# Dout32x.net
KiCad netlist of a schematic drawn in Altium Designer
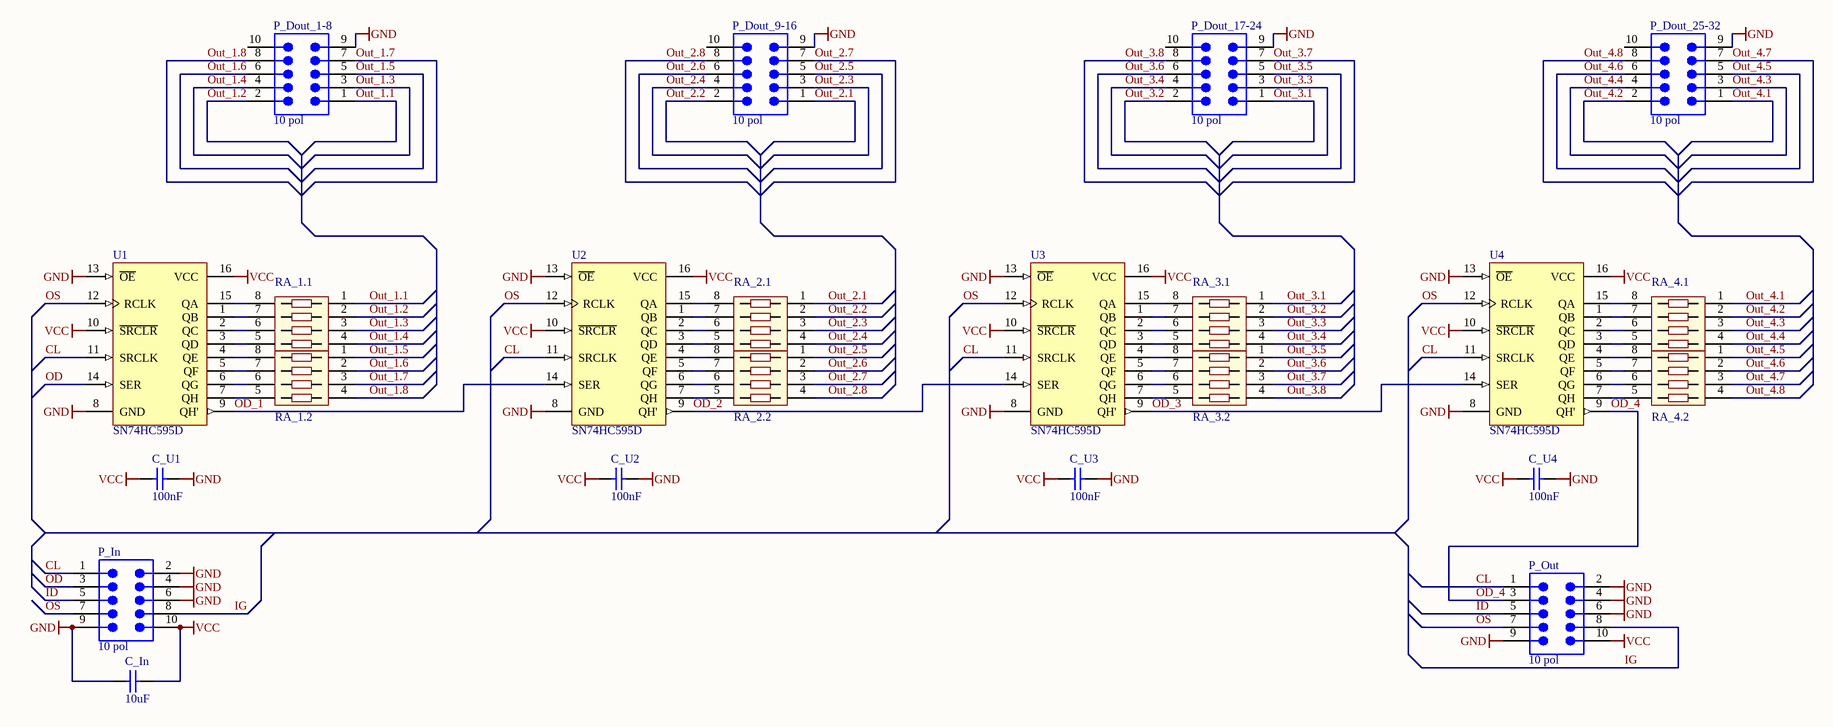
[diagram p0: Dout32x.SchDoc]

(export (version "E")
  (design (tool "Eeschema 10.0.6"))
  (components
    (comp (ref "C_In")
      (value "10uF")
      (footprint "1608[0603]")
      (description "Capacitor (Semiconductor SIM Model)")
      (fields (field (name "Comment") "Cap Semi") (field (name "PUBLISHER") "Altium Limited"))
      (libsource (lib "Miscellaneous Devices") (part "Cap Semi"))
    )
    (comp (ref "C_U1")
      (value "100nF")
      (footprint "1608[0603]")
      (description "Capacitor (Semiconductor SIM Model)")
      (fields (field (name "Comment") "Cap Semi") (field (name "PUBLISHER") "Altium Limited"))
      (libsource (lib "Miscellaneous Devices") (part "Cap Semi"))
    )
    (comp (ref "C_U2")
      (value "100nF")
      (footprint "1608[0603]")
      (description "Capacitor (Semiconductor SIM Model)")
      (fields (field (name "Comment") "Cap Semi") (field (name "PUBLISHER") "Altium Limited"))
      (libsource (lib "Miscellaneous Devices") (part "Cap Semi"))
    )
    (comp (ref "C_U3")
      (value "100nF")
      (footprint "1608[0603]")
      (description "Capacitor (Semiconductor SIM Model)")
      (fields (field (name "Comment") "Cap Semi") (field (name "PUBLISHER") "Altium Limited"))
      (libsource (lib "Miscellaneous Devices") (part "Cap Semi"))
    )
    (comp (ref "C_U4")
      (value "100nF")
      (footprint "1608[0603]")
      (description "Capacitor (Semiconductor SIM Model)")
      (fields (field (name "Comment") "Cap Semi") (field (name "PUBLISHER") "Altium Limited"))
      (libsource (lib "Miscellaneous Devices") (part "Cap Semi"))
    )
    (comp (ref "P_Dout_1-8")
      (value "10 pol")
      (footprint "918510x324")
      (fields (field (name "PUBLISHER") "Altium Limited"))
      (libsource (lib "HARTING IDC 2.54mm Pitch") (part "09 18 510 6324"))
    )
    (comp (ref "P_Dout_9-16")
      (value "10 pol")
      (footprint "918510x324")
      (fields (field (name "PUBLISHER") "Altium Limited"))
      (libsource (lib "HARTING IDC 2.54mm Pitch") (part "09 18 510 6324"))
    )
    (comp (ref "P_Dout_17-24")
      (value "10 pol")
      (footprint "918510x324")
      (fields (field (name "PUBLISHER") "Altium Limited"))
      (libsource (lib "HARTING IDC 2.54mm Pitch") (part "09 18 510 6324"))
    )
    (comp (ref "P_Dout_25-32")
      (value "10 pol")
      (footprint "918510x324")
      (fields (field (name "PUBLISHER") "Altium Limited"))
      (libsource (lib "HARTING IDC 2.54mm Pitch") (part "09 18 510 6324"))
    )
    (comp (ref "P_In")
      (value "10 pol")
      (footprint "918510x324")
      (fields (field (name "PUBLISHER") "Altium Limited"))
      (libsource (lib "") (part "09 18 510 6324_1"))
    )
    (comp (ref "P_Out")
      (value "10 pol")
      (footprint "918510x324")
      (fields (field (name "PUBLISHER") "Altium Limited"))
      (libsource (lib "") (part "09 18 510 6324_1"))
    )
    (comp (ref "RA_1.1")
      (value "EXB38")
      (footprint "Panasonic EXB38V:EXB38")
      (fields (field (name "PUBLISHER") "Altium Limited"))
      (libsource (lib "Panasonic Resistor Array") (part "4 Resistors Parallel"))
    )
    (comp (ref "RA_1.2")
      (value "EXB38")
      (footprint "Panasonic EXB38V:EXB38")
      (fields (field (name "PUBLISHER") "Altium Limited"))
      (libsource (lib "Panasonic Resistor Array") (part "4 Resistors Parallel"))
    )
    (comp (ref "RA_2.1")
      (value "EXB38")
      (footprint "Panasonic EXB38V:EXB38")
      (fields (field (name "PUBLISHER") "Altium Limited"))
      (libsource (lib "Panasonic Resistor Array") (part "4 Resistors Parallel"))
    )
    (comp (ref "RA_2.2")
      (value "EXB38")
      (footprint "Panasonic EXB38V:EXB38")
      (fields (field (name "PUBLISHER") "Altium Limited"))
      (libsource (lib "Panasonic Resistor Array") (part "4 Resistors Parallel"))
    )
    (comp (ref "RA_3.1")
      (value "EXB38")
      (footprint "Panasonic EXB38V:EXB38")
      (fields (field (name "PUBLISHER") "Altium Limited"))
      (libsource (lib "Panasonic Resistor Array") (part "4 Resistors Parallel"))
    )
    (comp (ref "RA_3.2")
      (value "EXB38")
      (footprint "Panasonic EXB38V:EXB38")
      (fields (field (name "PUBLISHER") "Altium Limited"))
      (libsource (lib "Panasonic Resistor Array") (part "4 Resistors Parallel"))
    )
    (comp (ref "RA_4.1")
      (value "EXB38")
      (footprint "Panasonic EXB38V:EXB38")
      (fields (field (name "PUBLISHER") "Altium Limited"))
      (libsource (lib "Panasonic Resistor Array") (part "4 Resistors Parallel"))
    )
    (comp (ref "RA_4.2")
      (value "EXB38")
      (footprint "Panasonic EXB38V:EXB38")
      (fields (field (name "PUBLISHER") "Altium Limited"))
      (libsource (lib "Panasonic Resistor Array") (part "4 Resistors Parallel"))
    )
    (comp (ref "U1")
      (value "SN74HC595D")
      (footprint "D016_N")
      (description "8-Bit Shift Register with 3-State Output Registers")
      (fields (field (name "PUBLISHER") "Altium Limited"))
      (libsource (lib "TI Logic Register") (part "SN74HC595D"))
    )
    (comp (ref "U2")
      (value "SN74HC595D")
      (footprint "D016_N")
      (description "8-Bit Shift Register with 3-State Output Registers")
      (fields (field (name "PUBLISHER") "Altium Limited"))
      (libsource (lib "TI Logic Register") (part "SN74HC595D"))
    )
    (comp (ref "U3")
      (value "SN74HC595D")
      (footprint "D016_N")
      (description "8-Bit Shift Register with 3-State Output Registers")
      (fields (field (name "PUBLISHER") "Altium Limited"))
      (libsource (lib "TI Logic Register") (part "SN74HC595D"))
    )
    (comp (ref "U4")
      (value "SN74HC595D")
      (footprint "D016_N")
      (description "8-Bit Shift Register with 3-State Output Registers")
      (fields (field (name "PUBLISHER") "Altium Limited"))
      (libsource (lib "TI Logic Register") (part "SN74HC595D"))
    )
  )
  (nets
    (net (code "1") (name "/CL") (class "Default")
      (node (ref "P_In") (pin "1") (pinfunction "1_1") (pintype "passive"))
      (node (ref "P_Out") (pin "1") (pinfunction "1_1") (pintype "passive"))
      (node (ref "U1") (pin "11") (pinfunction "SRCLK_11") (pintype "input"))
      (node (ref "U2") (pin "11") (pinfunction "SRCLK_11") (pintype "input"))
      (node (ref "U3") (pin "11") (pinfunction "SRCLK_11") (pintype "input"))
      (node (ref "U4") (pin "11") (pinfunction "SRCLK_11") (pintype "input"))
    )
    (net (code "2") (name "/ID") (class "Default")
      (node (ref "P_In") (pin "5") (pinfunction "5_5") (pintype "passive"))
      (node (ref "P_Out") (pin "5") (pinfunction "5_5") (pintype "passive"))
    )
    (net (code "3") (name "/IG") (class "Default")
      (node (ref "P_In") (pin "8") (pinfunction "8_8") (pintype "passive"))
      (node (ref "P_Out") (pin "8") (pinfunction "8_8") (pintype "passive"))
    )
    (net (code "4") (name "/OD") (class "Default")
      (node (ref "P_In") (pin "3") (pinfunction "3_3") (pintype "passive"))
      (node (ref "U1") (pin "14") (pinfunction "SER_14") (pintype "input"))
    )
    (net (code "5") (name "/OD_1") (class "Default")
      (node (ref "U1") (pin "9") (pinfunction "QH'_9") (pintype "output"))
      (node (ref "U2") (pin "14") (pinfunction "SER_14") (pintype "input"))
    )
    (net (code "6") (name "/OD_2") (class "Default")
      (node (ref "U2") (pin "9") (pinfunction "QH'_9") (pintype "output"))
      (node (ref "U3") (pin "14") (pinfunction "SER_14") (pintype "input"))
    )
    (net (code "7") (name "/OD_3") (class "Default")
      (node (ref "U3") (pin "9") (pinfunction "QH'_9") (pintype "output"))
      (node (ref "U4") (pin "14") (pinfunction "SER_14") (pintype "input"))
    )
    (net (code "8") (name "/OD_4") (class "Default")
      (node (ref "P_Out") (pin "3") (pinfunction "3_3") (pintype "passive"))
      (node (ref "U4") (pin "9") (pinfunction "QH'_9") (pintype "output"))
    )
    (net (code "9") (name "/OS") (class "Default")
      (node (ref "P_In") (pin "7") (pinfunction "7_7") (pintype "passive"))
      (node (ref "P_Out") (pin "7") (pinfunction "7_7") (pintype "passive"))
      (node (ref "U1") (pin "12") (pinfunction "RCLK_12") (pintype "input"))
      (node (ref "U2") (pin "12") (pinfunction "RCLK_12") (pintype "input"))
      (node (ref "U3") (pin "12") (pinfunction "RCLK_12") (pintype "input"))
      (node (ref "U4") (pin "12") (pinfunction "RCLK_12") (pintype "input"))
    )
    (net (code "10") (name "/Out_1.1") (class "Default")
      (node (ref "P_Dout_1-8") (pin "1") (pinfunction "1_1") (pintype "passive"))
      (node (ref "RA_1.1") (pin "1") (pinfunction "1_1") (pintype "passive"))
    )
    (net (code "11") (name "/Out_1.2") (class "Default")
      (node (ref "P_Dout_1-8") (pin "2") (pinfunction "2_2") (pintype "passive"))
      (node (ref "RA_1.1") (pin "2") (pinfunction "2_2") (pintype "passive"))
    )
    (net (code "12") (name "/Out_1.3") (class "Default")
      (node (ref "P_Dout_1-8") (pin "3") (pinfunction "3_3") (pintype "passive"))
      (node (ref "RA_1.1") (pin "3") (pinfunction "3_3") (pintype "passive"))
    )
    (net (code "13") (name "/Out_1.4") (class "Default")
      (node (ref "P_Dout_1-8") (pin "4") (pinfunction "4_4") (pintype "passive"))
      (node (ref "RA_1.1") (pin "4") (pinfunction "4_4") (pintype "passive"))
    )
    (net (code "14") (name "/Out_1.5") (class "Default")
      (node (ref "P_Dout_1-8") (pin "5") (pinfunction "5_5") (pintype "passive"))
      (node (ref "RA_1.2") (pin "1") (pinfunction "1_1") (pintype "passive"))
    )
    (net (code "15") (name "/Out_1.6") (class "Default")
      (node (ref "P_Dout_1-8") (pin "6") (pinfunction "6_6") (pintype "passive"))
      (node (ref "RA_1.2") (pin "2") (pinfunction "2_2") (pintype "passive"))
    )
    (net (code "16") (name "/Out_1.7") (class "Default")
      (node (ref "P_Dout_1-8") (pin "7") (pinfunction "7_7") (pintype "passive"))
      (node (ref "RA_1.2") (pin "3") (pinfunction "3_3") (pintype "passive"))
    )
    (net (code "17") (name "/Out_1.8") (class "Default")
      (node (ref "P_Dout_1-8") (pin "8") (pinfunction "8_8") (pintype "passive"))
      (node (ref "RA_1.2") (pin "4") (pinfunction "4_4") (pintype "passive"))
    )
    (net (code "18") (name "/Out_2.1") (class "Default")
      (node (ref "P_Dout_9-16") (pin "1") (pinfunction "1_1") (pintype "passive"))
      (node (ref "RA_2.1") (pin "1") (pinfunction "1_1") (pintype "passive"))
    )
    (net (code "19") (name "/Out_2.2") (class "Default")
      (node (ref "P_Dout_9-16") (pin "2") (pinfunction "2_2") (pintype "passive"))
      (node (ref "RA_2.1") (pin "2") (pinfunction "2_2") (pintype "passive"))
    )
    (net (code "20") (name "/Out_2.3") (class "Default")
      (node (ref "P_Dout_9-16") (pin "3") (pinfunction "3_3") (pintype "passive"))
      (node (ref "RA_2.1") (pin "3") (pinfunction "3_3") (pintype "passive"))
    )
    (net (code "21") (name "/Out_2.4") (class "Default")
      (node (ref "P_Dout_9-16") (pin "4") (pinfunction "4_4") (pintype "passive"))
      (node (ref "RA_2.1") (pin "4") (pinfunction "4_4") (pintype "passive"))
    )
    (net (code "22") (name "/Out_2.5") (class "Default")
      (node (ref "P_Dout_9-16") (pin "5") (pinfunction "5_5") (pintype "passive"))
      (node (ref "RA_2.2") (pin "1") (pinfunction "1_1") (pintype "passive"))
    )
    (net (code "23") (name "/Out_2.6") (class "Default")
      (node (ref "P_Dout_9-16") (pin "6") (pinfunction "6_6") (pintype "passive"))
      (node (ref "RA_2.2") (pin "2") (pinfunction "2_2") (pintype "passive"))
    )
    (net (code "24") (name "/Out_2.7") (class "Default")
      (node (ref "P_Dout_9-16") (pin "7") (pinfunction "7_7") (pintype "passive"))
      (node (ref "RA_2.2") (pin "3") (pinfunction "3_3") (pintype "passive"))
    )
    (net (code "25") (name "/Out_2.8") (class "Default")
      (node (ref "P_Dout_9-16") (pin "8") (pinfunction "8_8") (pintype "passive"))
      (node (ref "RA_2.2") (pin "4") (pinfunction "4_4") (pintype "passive"))
    )
    (net (code "26") (name "/Out_3.1") (class "Default")
      (node (ref "P_Dout_17-24") (pin "1") (pinfunction "1_1") (pintype "passive"))
      (node (ref "RA_3.1") (pin "1") (pinfunction "1_1") (pintype "passive"))
    )
    (net (code "27") (name "/Out_3.2") (class "Default")
      (node (ref "P_Dout_17-24") (pin "2") (pinfunction "2_2") (pintype "passive"))
      (node (ref "RA_3.1") (pin "2") (pinfunction "2_2") (pintype "passive"))
    )
    (net (code "28") (name "/Out_3.3") (class "Default")
      (node (ref "P_Dout_17-24") (pin "3") (pinfunction "3_3") (pintype "passive"))
      (node (ref "RA_3.1") (pin "3") (pinfunction "3_3") (pintype "passive"))
    )
    (net (code "29") (name "/Out_3.4") (class "Default")
      (node (ref "P_Dout_17-24") (pin "4") (pinfunction "4_4") (pintype "passive"))
      (node (ref "RA_3.1") (pin "4") (pinfunction "4_4") (pintype "passive"))
    )
    (net (code "30") (name "/Out_3.5") (class "Default")
      (node (ref "P_Dout_17-24") (pin "5") (pinfunction "5_5") (pintype "passive"))
      (node (ref "RA_3.2") (pin "1") (pinfunction "1_1") (pintype "passive"))
    )
    (net (code "31") (name "/Out_3.6") (class "Default")
      (node (ref "P_Dout_17-24") (pin "6") (pinfunction "6_6") (pintype "passive"))
      (node (ref "RA_3.2") (pin "2") (pinfunction "2_2") (pintype "passive"))
    )
    (net (code "32") (name "/Out_3.7") (class "Default")
      (node (ref "P_Dout_17-24") (pin "7") (pinfunction "7_7") (pintype "passive"))
      (node (ref "RA_3.2") (pin "3") (pinfunction "3_3") (pintype "passive"))
    )
    (net (code "33") (name "/Out_3.8") (class "Default")
      (node (ref "P_Dout_17-24") (pin "8") (pinfunction "8_8") (pintype "passive"))
      (node (ref "RA_3.2") (pin "4") (pinfunction "4_4") (pintype "passive"))
    )
    (net (code "34") (name "/Out_4.1") (class "Default")
      (node (ref "P_Dout_25-32") (pin "1") (pinfunction "1_1") (pintype "passive"))
      (node (ref "RA_4.1") (pin "1") (pinfunction "1_1") (pintype "passive"))
    )
    (net (code "35") (name "/Out_4.2") (class "Default")
      (node (ref "P_Dout_25-32") (pin "2") (pinfunction "2_2") (pintype "passive"))
      (node (ref "RA_4.1") (pin "2") (pinfunction "2_2") (pintype "passive"))
    )
    (net (code "36") (name "/Out_4.3") (class "Default")
      (node (ref "P_Dout_25-32") (pin "3") (pinfunction "3_3") (pintype "passive"))
      (node (ref "RA_4.1") (pin "3") (pinfunction "3_3") (pintype "passive"))
    )
    (net (code "37") (name "/Out_4.4") (class "Default")
      (node (ref "P_Dout_25-32") (pin "4") (pinfunction "4_4") (pintype "passive"))
      (node (ref "RA_4.1") (pin "4") (pinfunction "4_4") (pintype "passive"))
    )
    (net (code "38") (name "/Out_4.5") (class "Default")
      (node (ref "P_Dout_25-32") (pin "5") (pinfunction "5_5") (pintype "passive"))
      (node (ref "RA_4.2") (pin "1") (pinfunction "1_1") (pintype "passive"))
    )
    (net (code "39") (name "/Out_4.6") (class "Default")
      (node (ref "P_Dout_25-32") (pin "6") (pinfunction "6_6") (pintype "passive"))
      (node (ref "RA_4.2") (pin "2") (pinfunction "2_2") (pintype "passive"))
    )
    (net (code "40") (name "/Out_4.7") (class "Default")
      (node (ref "P_Dout_25-32") (pin "7") (pinfunction "7_7") (pintype "passive"))
      (node (ref "RA_4.2") (pin "3") (pinfunction "3_3") (pintype "passive"))
    )
    (net (code "41") (name "/Out_4.8") (class "Default")
      (node (ref "P_Dout_25-32") (pin "8") (pinfunction "8_8") (pintype "passive"))
      (node (ref "RA_4.2") (pin "4") (pinfunction "4_4") (pintype "passive"))
    )
    (net (code "42") (name "GND") (class "Default")
      (node (ref "C_In") (pin "1") (pinfunction "1_1") (pintype "passive"))
      (node (ref "C_U1") (pin "1") (pinfunction "1_1") (pintype "passive"))
      (node (ref "C_U2") (pin "1") (pinfunction "1_1") (pintype "passive"))
      (node (ref "C_U3") (pin "1") (pinfunction "1_1") (pintype "passive"))
      (node (ref "C_U4") (pin "1") (pinfunction "1_1") (pintype "passive"))
      (node (ref "P_Dout_1-8") (pin "9") (pinfunction "9_9") (pintype "passive"))
      (node (ref "P_Dout_17-24") (pin "9") (pinfunction "9_9") (pintype "passive"))
      (node (ref "P_Dout_25-32") (pin "9") (pinfunction "9_9") (pintype "passive"))
      (node (ref "P_Dout_9-16") (pin "9") (pinfunction "9_9") (pintype "passive"))
      (node (ref "P_In") (pin "2") (pinfunction "2_2") (pintype "passive"))
      (node (ref "P_In") (pin "4") (pinfunction "4_4") (pintype "passive"))
      (node (ref "P_In") (pin "6") (pinfunction "6_6") (pintype "passive"))
      (node (ref "P_In") (pin "9") (pinfunction "9_9") (pintype "passive"))
      (node (ref "P_Out") (pin "2") (pinfunction "2_2") (pintype "passive"))
      (node (ref "P_Out") (pin "4") (pinfunction "4_4") (pintype "passive"))
      (node (ref "P_Out") (pin "6") (pinfunction "6_6") (pintype "passive"))
      (node (ref "P_Out") (pin "9") (pinfunction "9_9") (pintype "passive"))
      (node (ref "U1") (pin "13") (pinfunction "~{OE}_13") (pintype "input"))
      (node (ref "U1") (pin "8") (pinfunction "GND_8") (pintype "power_in"))
      (node (ref "U2") (pin "13") (pinfunction "~{OE}_13") (pintype "input"))
      (node (ref "U2") (pin "8") (pinfunction "GND_8") (pintype "power_in"))
      (node (ref "U3") (pin "13") (pinfunction "~{OE}_13") (pintype "input"))
      (node (ref "U3") (pin "8") (pinfunction "GND_8") (pintype "power_in"))
      (node (ref "U4") (pin "13") (pinfunction "~{OE}_13") (pintype "input"))
      (node (ref "U4") (pin "8") (pinfunction "GND_8") (pintype "power_in"))
    )
    (net (code "43") (name "Net-(U1-QA)") (class "Default")
      (node (ref "RA_1.1") (pin "8") (pinfunction "8_8") (pintype "passive"))
      (node (ref "U1") (pin "15") (pinfunction "QA_15") (pintype "tri_state"))
    )
    (net (code "44") (name "Net-(U1-QB)") (class "Default")
      (node (ref "RA_1.1") (pin "7") (pinfunction "7_7") (pintype "passive"))
      (node (ref "U1") (pin "1") (pinfunction "QB_1") (pintype "tri_state"))
    )
    (net (code "45") (name "Net-(U1-QC)") (class "Default")
      (node (ref "RA_1.1") (pin "6") (pinfunction "6_6") (pintype "passive"))
      (node (ref "U1") (pin "2") (pinfunction "QC_2") (pintype "tri_state"))
    )
    (net (code "46") (name "Net-(U1-QD)") (class "Default")
      (node (ref "RA_1.1") (pin "5") (pinfunction "5_5") (pintype "passive"))
      (node (ref "U1") (pin "3") (pinfunction "QD_3") (pintype "tri_state"))
    )
    (net (code "47") (name "Net-(U1-QE)") (class "Default")
      (node (ref "RA_1.2") (pin "8") (pinfunction "8_8") (pintype "passive"))
      (node (ref "U1") (pin "4") (pinfunction "QE_4") (pintype "tri_state"))
    )
    (net (code "48") (name "Net-(U1-QF)") (class "Default")
      (node (ref "RA_1.2") (pin "7") (pinfunction "7_7") (pintype "passive"))
      (node (ref "U1") (pin "5") (pinfunction "QF_5") (pintype "tri_state"))
    )
    (net (code "49") (name "Net-(U1-QG)") (class "Default")
      (node (ref "RA_1.2") (pin "6") (pinfunction "6_6") (pintype "passive"))
      (node (ref "U1") (pin "6") (pinfunction "QG_6") (pintype "tri_state"))
    )
    (net (code "50") (name "Net-(U1-QH)") (class "Default")
      (node (ref "RA_1.2") (pin "5") (pinfunction "5_5") (pintype "passive"))
      (node (ref "U1") (pin "7") (pinfunction "QH_7") (pintype "tri_state"))
    )
    (net (code "51") (name "Net-(U2-QA)") (class "Default")
      (node (ref "RA_2.1") (pin "8") (pinfunction "8_8") (pintype "passive"))
      (node (ref "U2") (pin "15") (pinfunction "QA_15") (pintype "tri_state"))
    )
    (net (code "52") (name "Net-(U2-QB)") (class "Default")
      (node (ref "RA_2.1") (pin "7") (pinfunction "7_7") (pintype "passive"))
      (node (ref "U2") (pin "1") (pinfunction "QB_1") (pintype "tri_state"))
    )
    (net (code "53") (name "Net-(U2-QC)") (class "Default")
      (node (ref "RA_2.1") (pin "6") (pinfunction "6_6") (pintype "passive"))
      (node (ref "U2") (pin "2") (pinfunction "QC_2") (pintype "tri_state"))
    )
    (net (code "54") (name "Net-(U2-QD)") (class "Default")
      (node (ref "RA_2.1") (pin "5") (pinfunction "5_5") (pintype "passive"))
      (node (ref "U2") (pin "3") (pinfunction "QD_3") (pintype "tri_state"))
    )
    (net (code "55") (name "Net-(U2-QE)") (class "Default")
      (node (ref "RA_2.2") (pin "8") (pinfunction "8_8") (pintype "passive"))
      (node (ref "U2") (pin "4") (pinfunction "QE_4") (pintype "tri_state"))
    )
    (net (code "56") (name "Net-(U2-QF)") (class "Default")
      (node (ref "RA_2.2") (pin "7") (pinfunction "7_7") (pintype "passive"))
      (node (ref "U2") (pin "5") (pinfunction "QF_5") (pintype "tri_state"))
    )
    (net (code "57") (name "Net-(U2-QG)") (class "Default")
      (node (ref "RA_2.2") (pin "6") (pinfunction "6_6") (pintype "passive"))
      (node (ref "U2") (pin "6") (pinfunction "QG_6") (pintype "tri_state"))
    )
    (net (code "58") (name "Net-(U2-QH)") (class "Default")
      (node (ref "RA_2.2") (pin "5") (pinfunction "5_5") (pintype "passive"))
      (node (ref "U2") (pin "7") (pinfunction "QH_7") (pintype "tri_state"))
    )
    (net (code "59") (name "Net-(U3-QA)") (class "Default")
      (node (ref "RA_3.1") (pin "8") (pinfunction "8_8") (pintype "passive"))
      (node (ref "U3") (pin "15") (pinfunction "QA_15") (pintype "tri_state"))
    )
    (net (code "60") (name "Net-(U3-QB)") (class "Default")
      (node (ref "RA_3.1") (pin "7") (pinfunction "7_7") (pintype "passive"))
      (node (ref "U3") (pin "1") (pinfunction "QB_1") (pintype "tri_state"))
    )
    (net (code "61") (name "Net-(U3-QC)") (class "Default")
      (node (ref "RA_3.1") (pin "6") (pinfunction "6_6") (pintype "passive"))
      (node (ref "U3") (pin "2") (pinfunction "QC_2") (pintype "tri_state"))
    )
    (net (code "62") (name "Net-(U3-QD)") (class "Default")
      (node (ref "RA_3.1") (pin "5") (pinfunction "5_5") (pintype "passive"))
      (node (ref "U3") (pin "3") (pinfunction "QD_3") (pintype "tri_state"))
    )
    (net (code "63") (name "Net-(U3-QE)") (class "Default")
      (node (ref "RA_3.2") (pin "8") (pinfunction "8_8") (pintype "passive"))
      (node (ref "U3") (pin "4") (pinfunction "QE_4") (pintype "tri_state"))
    )
    (net (code "64") (name "Net-(U3-QF)") (class "Default")
      (node (ref "RA_3.2") (pin "7") (pinfunction "7_7") (pintype "passive"))
      (node (ref "U3") (pin "5") (pinfunction "QF_5") (pintype "tri_state"))
    )
    (net (code "65") (name "Net-(U3-QG)") (class "Default")
      (node (ref "RA_3.2") (pin "6") (pinfunction "6_6") (pintype "passive"))
      (node (ref "U3") (pin "6") (pinfunction "QG_6") (pintype "tri_state"))
    )
    (net (code "66") (name "Net-(U3-QH)") (class "Default")
      (node (ref "RA_3.2") (pin "5") (pinfunction "5_5") (pintype "passive"))
      (node (ref "U3") (pin "7") (pinfunction "QH_7") (pintype "tri_state"))
    )
    (net (code "67") (name "Net-(U4-QA)") (class "Default")
      (node (ref "RA_4.1") (pin "8") (pinfunction "8_8") (pintype "passive"))
      (node (ref "U4") (pin "15") (pinfunction "QA_15") (pintype "tri_state"))
    )
    (net (code "68") (name "Net-(U4-QB)") (class "Default")
      (node (ref "RA_4.1") (pin "7") (pinfunction "7_7") (pintype "passive"))
      (node (ref "U4") (pin "1") (pinfunction "QB_1") (pintype "tri_state"))
    )
    (net (code "69") (name "Net-(U4-QC)") (class "Default")
      (node (ref "RA_4.1") (pin "6") (pinfunction "6_6") (pintype "passive"))
      (node (ref "U4") (pin "2") (pinfunction "QC_2") (pintype "tri_state"))
    )
    (net (code "70") (name "Net-(U4-QD)") (class "Default")
      (node (ref "RA_4.1") (pin "5") (pinfunction "5_5") (pintype "passive"))
      (node (ref "U4") (pin "3") (pinfunction "QD_3") (pintype "tri_state"))
    )
    (net (code "71") (name "Net-(U4-QE)") (class "Default")
      (node (ref "RA_4.2") (pin "8") (pinfunction "8_8") (pintype "passive"))
      (node (ref "U4") (pin "4") (pinfunction "QE_4") (pintype "tri_state"))
    )
    (net (code "72") (name "Net-(U4-QF)") (class "Default")
      (node (ref "RA_4.2") (pin "7") (pinfunction "7_7") (pintype "passive"))
      (node (ref "U4") (pin "5") (pinfunction "QF_5") (pintype "tri_state"))
    )
    (net (code "73") (name "Net-(U4-QG)") (class "Default")
      (node (ref "RA_4.2") (pin "6") (pinfunction "6_6") (pintype "passive"))
      (node (ref "U4") (pin "6") (pinfunction "QG_6") (pintype "tri_state"))
    )
    (net (code "74") (name "Net-(U4-QH)") (class "Default")
      (node (ref "RA_4.2") (pin "5") (pinfunction "5_5") (pintype "passive"))
      (node (ref "U4") (pin "7") (pinfunction "QH_7") (pintype "tri_state"))
    )
    (net (code "75") (name "VCC") (class "Default")
      (node (ref "C_In") (pin "2") (pinfunction "2_2") (pintype "passive"))
      (node (ref "C_U1") (pin "2") (pinfunction "2_2") (pintype "passive"))
      (node (ref "C_U2") (pin "2") (pinfunction "2_2") (pintype "passive"))
      (node (ref "C_U3") (pin "2") (pinfunction "2_2") (pintype "passive"))
      (node (ref "C_U4") (pin "2") (pinfunction "2_2") (pintype "passive"))
      (node (ref "P_In") (pin "10") (pinfunction "10_10") (pintype "passive"))
      (node (ref "P_Out") (pin "10") (pinfunction "10_10") (pintype "passive"))
      (node (ref "U1") (pin "10") (pinfunction "~{SRCLR}_10") (pintype "input"))
      (node (ref "U1") (pin "16") (pinfunction "VCC_16") (pintype "power_in"))
      (node (ref "U2") (pin "10") (pinfunction "~{SRCLR}_10") (pintype "input"))
      (node (ref "U2") (pin "16") (pinfunction "VCC_16") (pintype "power_in"))
      (node (ref "U3") (pin "10") (pinfunction "~{SRCLR}_10") (pintype "input"))
      (node (ref "U3") (pin "16") (pinfunction "VCC_16") (pintype "power_in"))
      (node (ref "U4") (pin "10") (pinfunction "~{SRCLR}_10") (pintype "input"))
      (node (ref "U4") (pin "16") (pinfunction "VCC_16") (pintype "power_in"))
    )
    (net (code "76") (name "unconnected-(P_Dout_1-8-Pad10)") (class "Default")
      (node (ref "P_Dout_1-8") (pin "10") (pinfunction "10_10") (pintype "passive"))
    )
    (net (code "77") (name "unconnected-(P_Dout_9-16-Pad10)") (class "Default")
      (node (ref "P_Dout_9-16") (pin "10") (pinfunction "10_10") (pintype "passive"))
    )
    (net (code "78") (name "unconnected-(P_Dout_17-24-Pad10)") (class "Default")
      (node (ref "P_Dout_17-24") (pin "10") (pinfunction "10_10") (pintype "passive"))
    )
    (net (code "79") (name "unconnected-(P_Dout_25-32-Pad10)") (class "Default")
      (node (ref "P_Dout_25-32") (pin "10") (pinfunction "10_10") (pintype "passive"))
    )
  )
)
